# Schematic_V0_2.net
KiCad netlist of a schematic drawn in EAGLE
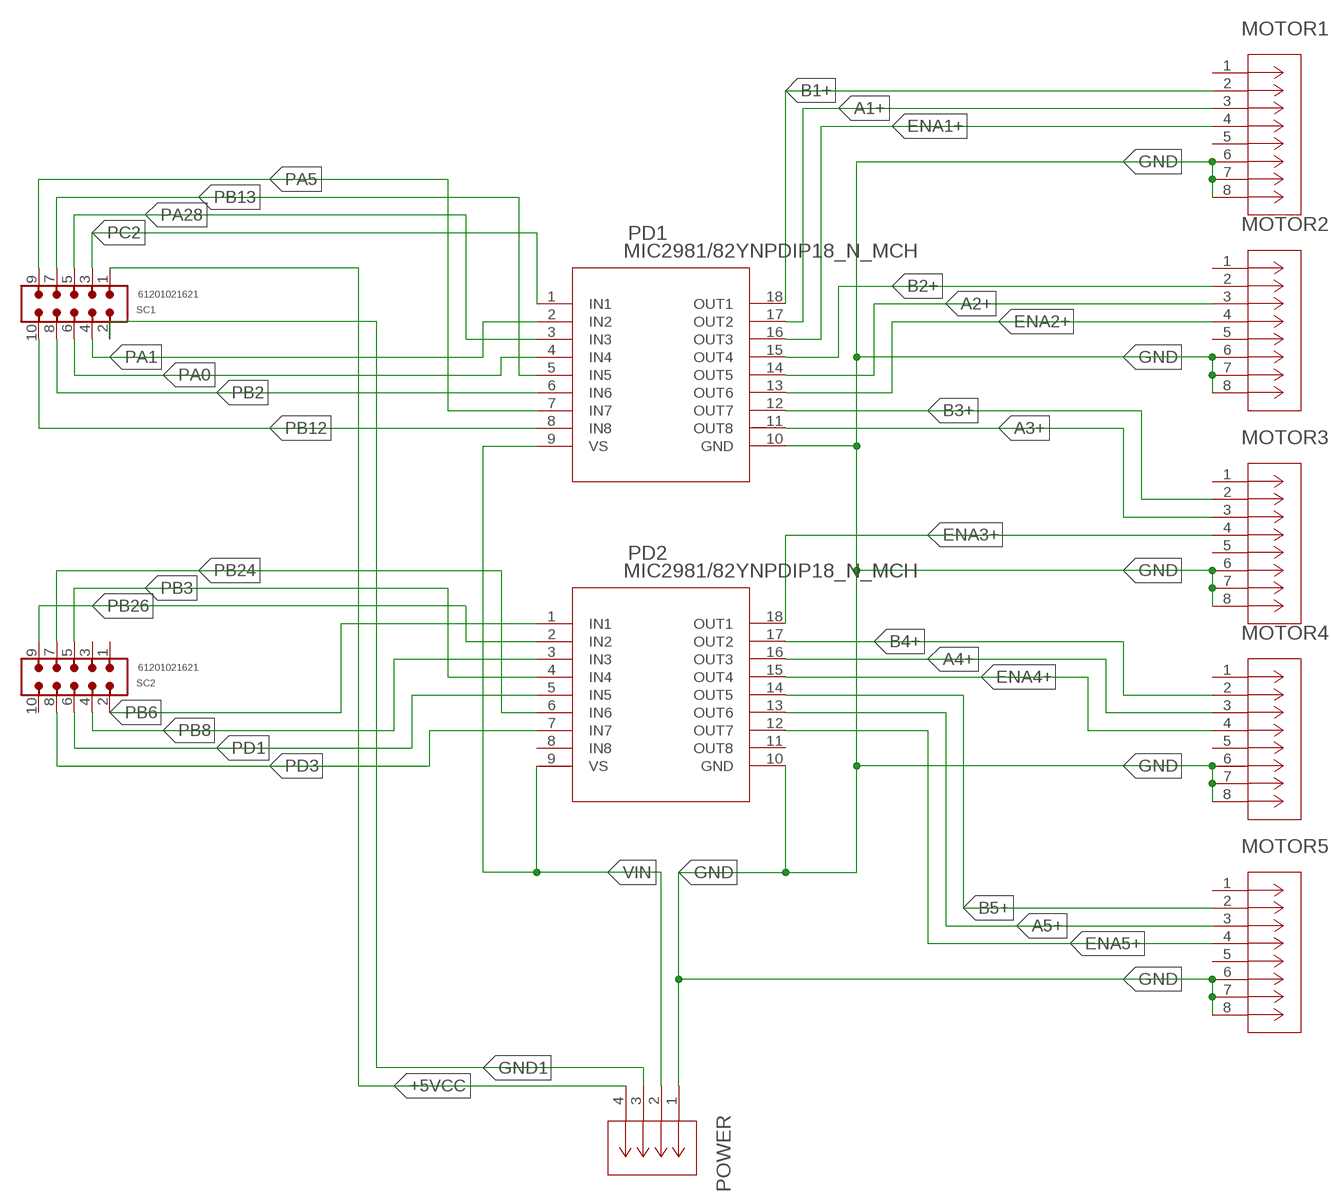
[diagram p0: schematic, sheet 1]

(export (version "E")
  (design (tool "Eeschema 10.0.6"))
  (components
    (comp (ref "MOTOR1")
      (value "1724470208CON_1724470208")
      (footprint "eagle-import:CON_1724470208")
      (fields
        (field (name "MANUFACTURER_PART_NUMBER") "1724470208")
        (field (name "COPYRIGHT") "Copyright (C) 2024 Ultra Librarian. All rights reserved.")
      )
      (libsource (lib "eagle-import") (part "1724470208CON_1724470208"))
    )
    (comp (ref "MOTOR2")
      (value "1724470208CON_1724470208")
      (footprint "eagle-import:CON_1724470208")
      (fields
        (field (name "MANUFACTURER_PART_NUMBER") "1724470208")
        (field (name "COPYRIGHT") "Copyright (C) 2024 Ultra Librarian. All rights reserved.")
      )
      (libsource (lib "eagle-import") (part "1724470208CON_1724470208"))
    )
    (comp (ref "MOTOR3")
      (value "1724470208CON_1724470208")
      (footprint "eagle-import:CON_1724470208")
      (fields
        (field (name "MANUFACTURER_PART_NUMBER") "1724470208")
        (field (name "COPYRIGHT") "Copyright (C) 2024 Ultra Librarian. All rights reserved.")
      )
      (libsource (lib "eagle-import") (part "1724470208CON_1724470208"))
    )
    (comp (ref "MOTOR4")
      (value "1724470208CON_1724470208")
      (footprint "eagle-import:CON_1724470208")
      (fields
        (field (name "MANUFACTURER_PART_NUMBER") "1724470208")
        (field (name "COPYRIGHT") "Copyright (C) 2024 Ultra Librarian. All rights reserved.")
      )
      (libsource (lib "eagle-import") (part "1724470208CON_1724470208"))
    )
    (comp (ref "MOTOR5")
      (value "1724470208CON_1724470208")
      (footprint "eagle-import:CON_1724470208")
      (fields
        (field (name "MANUFACTURER_PART_NUMBER") "1724470208")
        (field (name "COPYRIGHT") "Copyright (C) 2024 Ultra Librarian. All rights reserved.")
      )
      (libsource (lib "eagle-import") (part "1724470208CON_1724470208"))
    )
    (comp (ref "PD1")
      (value "MIC2981/82YNPDIP18_N_MCH")
      (footprint "eagle-import:PDIP18_N_MCH")
      (fields
        (field (name "MANUFACTURER_PART_NUMBER") "MIC2981/82YN")
        (field (name "COPYRIGHT") "Copyright (C) 2024 Ultra Librarian. All rights reserved.")
      )
      (libsource (lib "eagle-import") (part "MIC2981/82YNPDIP18_N_MCH"))
    )
    (comp (ref "PD2")
      (value "MIC2981/82YNPDIP18_N_MCH")
      (footprint "eagle-import:PDIP18_N_MCH")
      (fields
        (field (name "MANUFACTURER_PART_NUMBER") "MIC2981/82YN")
        (field (name "COPYRIGHT") "Copyright (C) 2024 Ultra Librarian. All rights reserved.")
      )
      (libsource (lib "eagle-import") (part "MIC2981/82YNPDIP18_N_MCH"))
    )
    (comp (ref "POWER")
      (value "OSTYK42104030CONN4_K42104030_OST")
      (footprint "eagle-import:CONN4_K42104030_OST")
      (fields
        (field (name "MANUFACTURER_PART_NUMBER") "OSTYK42104030")
        (field (name "COPYRIGHT") "Copyright (C) 2024 Ultra Librarian. All rights reserved.")
      )
      (libsource (lib "eagle-import") (part "OSTYK42104030CONN4_K42104030_OST"))
    )
    (comp (ref "SC1")
      (value "61201021621")
      (footprint "eagle-import:61201021621")
      (libsource (lib "eagle-import") (part "6120XX21621_61201021621"))
    )
    (comp (ref "SC2")
      (value "61201021621")
      (footprint "eagle-import:61201021621")
      (libsource (lib "eagle-import") (part "6120XX21621_61201021621"))
    )
  )
  (nets
    (net (code "1") (name "+5VCC") (class "Default")
      (node (ref "POWER") (pin "4") (pinfunction "4_4") (pintype "passive"))
      (node (ref "SC1") (pin "1") (pinfunction "1_1") (pintype "passive"))
    )
    (net (code "2") (name "A1+") (class "Default")
      (node (ref "MOTOR1") (pin "3") (pinfunction "3_3") (pintype "passive"))
      (node (ref "PD1") (pin "17") (pinfunction "OUT2_17") (pintype "output"))
    )
    (net (code "3") (name "A2+") (class "Default")
      (node (ref "MOTOR2") (pin "3") (pinfunction "3_3") (pintype "passive"))
      (node (ref "PD1") (pin "14") (pinfunction "OUT5_14") (pintype "output"))
    )
    (net (code "4") (name "A3+") (class "Default")
      (node (ref "MOTOR3") (pin "3") (pinfunction "3_3") (pintype "passive"))
      (node (ref "PD1") (pin "11") (pinfunction "OUT8_11") (pintype "output"))
    )
    (net (code "5") (name "A4+") (class "Default")
      (node (ref "MOTOR4") (pin "3") (pinfunction "3_3") (pintype "passive"))
      (node (ref "PD2") (pin "16") (pinfunction "OUT3_16") (pintype "output"))
    )
    (net (code "6") (name "A5+") (class "Default")
      (node (ref "MOTOR5") (pin "3") (pinfunction "3_3") (pintype "passive"))
      (node (ref "PD2") (pin "13") (pinfunction "OUT6_13") (pintype "output"))
    )
    (net (code "7") (name "B1+") (class "Default")
      (node (ref "MOTOR1") (pin "2") (pinfunction "2_2") (pintype "passive"))
      (node (ref "PD1") (pin "18") (pinfunction "OUT1_18") (pintype "output"))
    )
    (net (code "8") (name "B2+") (class "Default")
      (node (ref "MOTOR2") (pin "2") (pinfunction "2_2") (pintype "passive"))
      (node (ref "PD1") (pin "15") (pinfunction "OUT4_15") (pintype "output"))
    )
    (net (code "9") (name "B3+") (class "Default")
      (node (ref "MOTOR3") (pin "2") (pinfunction "2_2") (pintype "passive"))
      (node (ref "PD1") (pin "12") (pinfunction "OUT7_12") (pintype "output"))
    )
    (net (code "10") (name "B4+") (class "Default")
      (node (ref "MOTOR4") (pin "2") (pinfunction "2_2") (pintype "passive"))
      (node (ref "PD2") (pin "17") (pinfunction "OUT2_17") (pintype "output"))
    )
    (net (code "11") (name "B5+") (class "Default")
      (node (ref "MOTOR5") (pin "2") (pinfunction "2_2") (pintype "passive"))
      (node (ref "PD2") (pin "14") (pinfunction "OUT5_14") (pintype "output"))
    )
    (net (code "12") (name "ENA1+") (class "Default")
      (node (ref "MOTOR1") (pin "4") (pinfunction "4_4") (pintype "passive"))
      (node (ref "PD1") (pin "16") (pinfunction "OUT3_16") (pintype "output"))
    )
    (net (code "13") (name "ENA2+") (class "Default")
      (node (ref "MOTOR2") (pin "4") (pinfunction "4_4") (pintype "passive"))
      (node (ref "PD1") (pin "13") (pinfunction "OUT6_13") (pintype "output"))
    )
    (net (code "14") (name "ENA3+") (class "Default")
      (node (ref "MOTOR3") (pin "4") (pinfunction "4_4") (pintype "passive"))
      (node (ref "PD2") (pin "18") (pinfunction "OUT1_18") (pintype "output"))
    )
    (net (code "15") (name "ENA4+") (class "Default")
      (node (ref "MOTOR4") (pin "4") (pinfunction "4_4") (pintype "passive"))
      (node (ref "PD2") (pin "15") (pinfunction "OUT4_15") (pintype "output"))
    )
    (net (code "16") (name "ENA5+") (class "Default")
      (node (ref "MOTOR5") (pin "4") (pinfunction "4_4") (pintype "passive"))
      (node (ref "PD2") (pin "12") (pinfunction "OUT7_12") (pintype "output"))
    )
    (net (code "17") (name "GND") (class "Default")
      (node (ref "MOTOR1") (pin "6") (pinfunction "6_6") (pintype "passive"))
      (node (ref "MOTOR1") (pin "7") (pinfunction "7_7") (pintype "passive"))
      (node (ref "MOTOR1") (pin "8") (pinfunction "8_8") (pintype "passive"))
      (node (ref "MOTOR2") (pin "6") (pinfunction "6_6") (pintype "passive"))
      (node (ref "MOTOR2") (pin "7") (pinfunction "7_7") (pintype "passive"))
      (node (ref "MOTOR2") (pin "8") (pinfunction "8_8") (pintype "passive"))
      (node (ref "MOTOR3") (pin "6") (pinfunction "6_6") (pintype "passive"))
      (node (ref "MOTOR3") (pin "7") (pinfunction "7_7") (pintype "passive"))
      (node (ref "MOTOR3") (pin "8") (pinfunction "8_8") (pintype "passive"))
      (node (ref "MOTOR4") (pin "6") (pinfunction "6_6") (pintype "passive"))
      (node (ref "MOTOR4") (pin "7") (pinfunction "7_7") (pintype "passive"))
      (node (ref "MOTOR4") (pin "8") (pinfunction "8_8") (pintype "passive"))
      (node (ref "MOTOR5") (pin "6") (pinfunction "6_6") (pintype "passive"))
      (node (ref "MOTOR5") (pin "7") (pinfunction "7_7") (pintype "passive"))
      (node (ref "MOTOR5") (pin "8") (pinfunction "8_8") (pintype "passive"))
      (node (ref "PD1") (pin "10") (pinfunction "GND_10") (pintype "passive"))
      (node (ref "PD2") (pin "10") (pinfunction "GND_10") (pintype "passive"))
      (node (ref "POWER") (pin "1") (pinfunction "1_1") (pintype "passive"))
    )
    (net (code "18") (name "GND1") (class "Default")
      (node (ref "POWER") (pin "3") (pinfunction "3_3") (pintype "passive"))
      (node (ref "SC1") (pin "2") (pinfunction "2_2") (pintype "passive"))
    )
    (net (code "19") (name "PA0") (class "Default")
      (node (ref "PD1") (pin "4") (pinfunction "IN4_4") (pintype "input"))
      (node (ref "SC1") (pin "6") (pinfunction "6_6") (pintype "passive"))
    )
    (net (code "20") (name "PA1") (class "Default")
      (node (ref "PD1") (pin "2") (pinfunction "IN2_2") (pintype "input"))
      (node (ref "SC1") (pin "4") (pinfunction "4_4") (pintype "passive"))
    )
    (net (code "21") (name "PA5") (class "Default")
      (node (ref "PD1") (pin "7") (pinfunction "IN7_7") (pintype "input"))
      (node (ref "SC1") (pin "9") (pinfunction "9_9") (pintype "passive"))
    )
    (net (code "22") (name "PA28") (class "Default")
      (node (ref "PD1") (pin "3") (pinfunction "IN3_3") (pintype "input"))
      (node (ref "SC1") (pin "5") (pinfunction "5_5") (pintype "passive"))
    )
    (net (code "23") (name "PB2") (class "Default")
      (node (ref "PD1") (pin "6") (pinfunction "IN6_6") (pintype "input"))
      (node (ref "SC1") (pin "8") (pinfunction "8_8") (pintype "passive"))
    )
    (net (code "24") (name "PB3") (class "Default")
      (node (ref "PD2") (pin "4") (pinfunction "IN4_4") (pintype "input"))
      (node (ref "SC2") (pin "5") (pinfunction "5_5") (pintype "passive"))
    )
    (net (code "25") (name "PB6") (class "Default")
      (node (ref "PD2") (pin "1") (pinfunction "IN1_1") (pintype "input"))
      (node (ref "SC2") (pin "2") (pinfunction "2_2") (pintype "passive"))
    )
    (net (code "26") (name "PB8") (class "Default")
      (node (ref "PD2") (pin "3") (pinfunction "IN3_3") (pintype "input"))
      (node (ref "SC2") (pin "4") (pinfunction "4_4") (pintype "passive"))
    )
    (net (code "27") (name "PB12") (class "Default")
      (node (ref "PD1") (pin "8") (pinfunction "IN8_8") (pintype "input"))
      (node (ref "SC1") (pin "10") (pinfunction "10_10") (pintype "passive"))
    )
    (net (code "28") (name "PB13") (class "Default")
      (node (ref "PD1") (pin "5") (pinfunction "IN5_5") (pintype "input"))
      (node (ref "SC1") (pin "7") (pinfunction "7_7") (pintype "passive"))
    )
    (net (code "29") (name "PB24") (class "Default")
      (node (ref "PD2") (pin "6") (pinfunction "IN6_6") (pintype "input"))
      (node (ref "SC2") (pin "7") (pinfunction "7_7") (pintype "passive"))
    )
    (net (code "30") (name "PB26") (class "Default")
      (node (ref "PD2") (pin "2") (pinfunction "IN2_2") (pintype "input"))
      (node (ref "SC2") (pin "9") (pinfunction "9_9") (pintype "passive"))
    )
    (net (code "31") (name "PC2") (class "Default")
      (node (ref "PD1") (pin "1") (pinfunction "IN1_1") (pintype "input"))
      (node (ref "SC1") (pin "3") (pinfunction "3_3") (pintype "passive"))
    )
    (net (code "32") (name "PD1") (class "Default")
      (node (ref "PD2") (pin "5") (pinfunction "IN5_5") (pintype "input"))
      (node (ref "SC2") (pin "6") (pinfunction "6_6") (pintype "passive"))
    )
    (net (code "33") (name "PD3") (class "Default")
      (node (ref "PD2") (pin "7") (pinfunction "IN7_7") (pintype "input"))
      (node (ref "SC2") (pin "8") (pinfunction "8_8") (pintype "passive"))
    )
    (net (code "34") (name "VIN") (class "Default")
      (node (ref "PD1") (pin "9") (pinfunction "VS_9") (pintype "power_in"))
      (node (ref "PD2") (pin "9") (pinfunction "VS_9") (pintype "power_in"))
      (node (ref "POWER") (pin "2") (pinfunction "2_2") (pintype "passive"))
    )
    (net (code "35") (name "unconnected-(MOTOR1-Pad1)") (class "Default")
      (node (ref "MOTOR1") (pin "1") (pinfunction "1_1") (pintype "passive"))
    )
    (net (code "36") (name "unconnected-(MOTOR1-Pad5)") (class "Default")
      (node (ref "MOTOR1") (pin "5") (pinfunction "5_5") (pintype "passive"))
    )
    (net (code "37") (name "unconnected-(MOTOR2-Pad1)") (class "Default")
      (node (ref "MOTOR2") (pin "1") (pinfunction "1_1") (pintype "passive"))
    )
    (net (code "38") (name "unconnected-(MOTOR2-Pad5)") (class "Default")
      (node (ref "MOTOR2") (pin "5") (pinfunction "5_5") (pintype "passive"))
    )
    (net (code "39") (name "unconnected-(MOTOR3-Pad1)") (class "Default")
      (node (ref "MOTOR3") (pin "1") (pinfunction "1_1") (pintype "passive"))
    )
    (net (code "40") (name "unconnected-(MOTOR3-Pad5)") (class "Default")
      (node (ref "MOTOR3") (pin "5") (pinfunction "5_5") (pintype "passive"))
    )
    (net (code "41") (name "unconnected-(MOTOR4-Pad1)") (class "Default")
      (node (ref "MOTOR4") (pin "1") (pinfunction "1_1") (pintype "passive"))
    )
    (net (code "42") (name "unconnected-(MOTOR4-Pad5)") (class "Default")
      (node (ref "MOTOR4") (pin "5") (pinfunction "5_5") (pintype "passive"))
    )
    (net (code "43") (name "unconnected-(MOTOR5-Pad1)") (class "Default")
      (node (ref "MOTOR5") (pin "1") (pinfunction "1_1") (pintype "passive"))
    )
    (net (code "44") (name "unconnected-(MOTOR5-Pad5)") (class "Default")
      (node (ref "MOTOR5") (pin "5") (pinfunction "5_5") (pintype "passive"))
    )
    (net (code "45") (name "unconnected-(PD2-IN8-Pad8)") (class "Default")
      (node (ref "PD2") (pin "8") (pinfunction "IN8_8") (pintype "input"))
    )
    (net (code "46") (name "unconnected-(PD2-OUT8-Pad11)") (class "Default")
      (node (ref "PD2") (pin "11") (pinfunction "OUT8_11") (pintype "output"))
    )
    (net (code "47") (name "unconnected-(SC2-Pad1)") (class "Default")
      (node (ref "SC2") (pin "1") (pinfunction "1_1") (pintype "passive"))
    )
    (net (code "48") (name "unconnected-(SC2-Pad3)") (class "Default")
      (node (ref "SC2") (pin "3") (pinfunction "3_3") (pintype "passive"))
    )
    (net (code "49") (name "unconnected-(SC2-Pad10)") (class "Default")
      (node (ref "SC2") (pin "10") (pinfunction "10_10") (pintype "passive"))
    )
  )
)
